# schematic.net
KiCad netlist of a schematic drawn in EAGLE
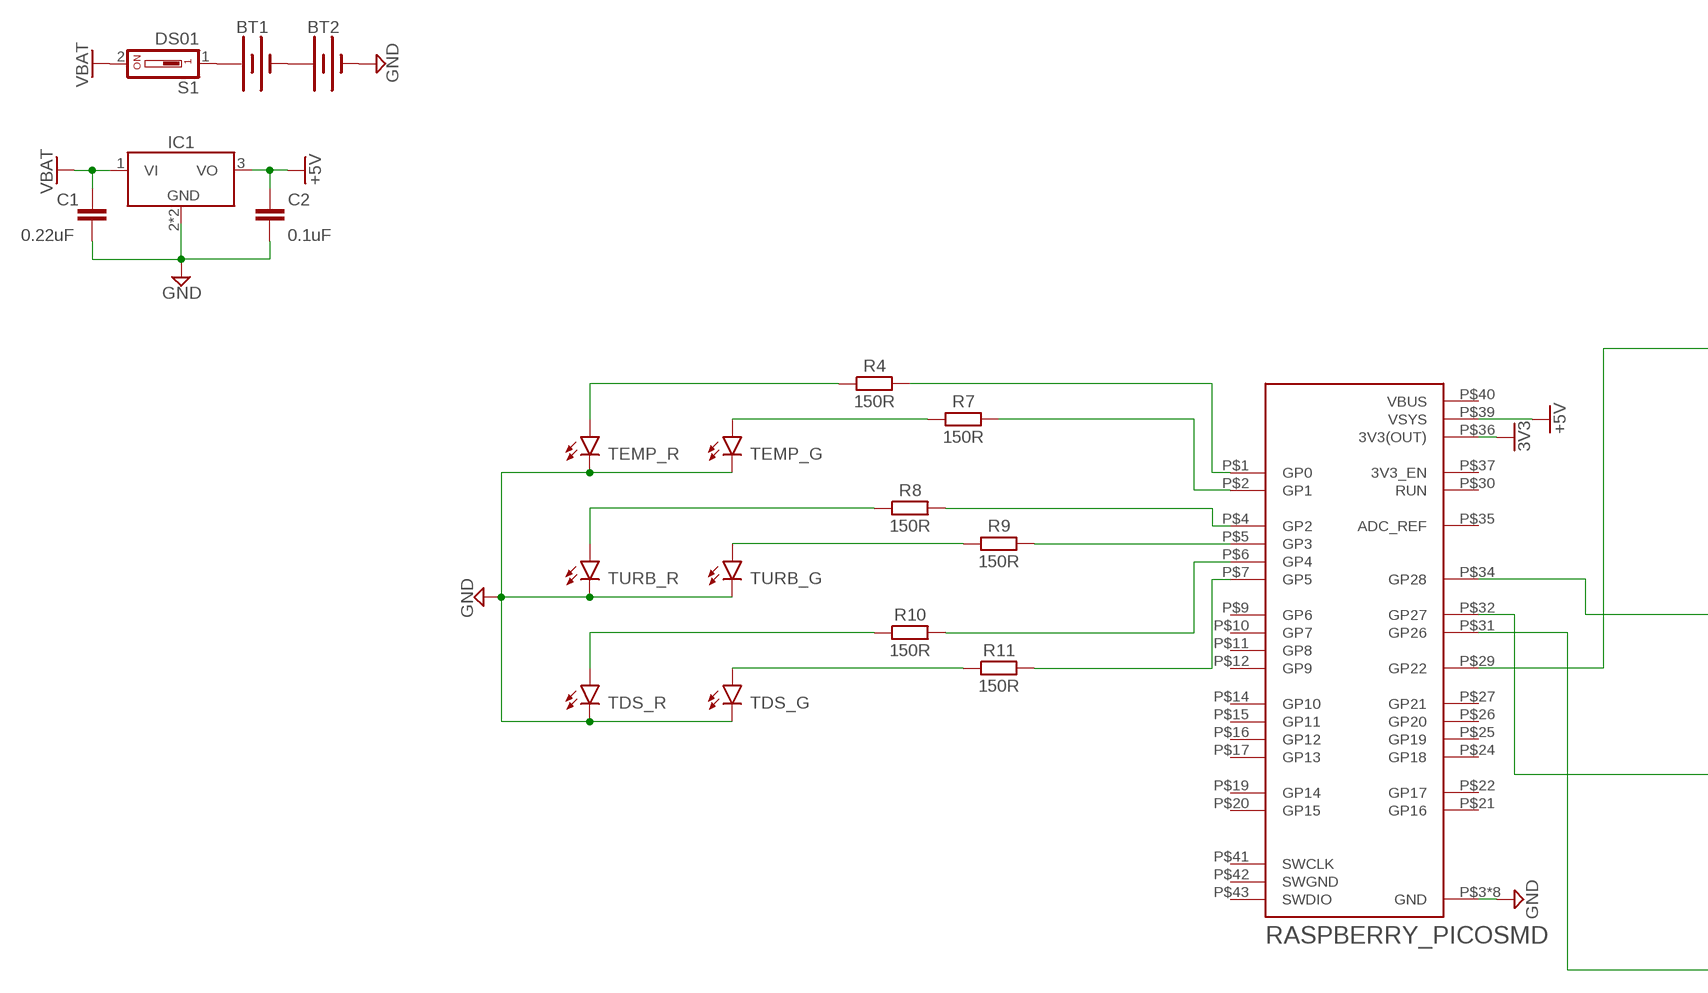
[diagram p0: schematic, sheet 1, part 1 of 2]
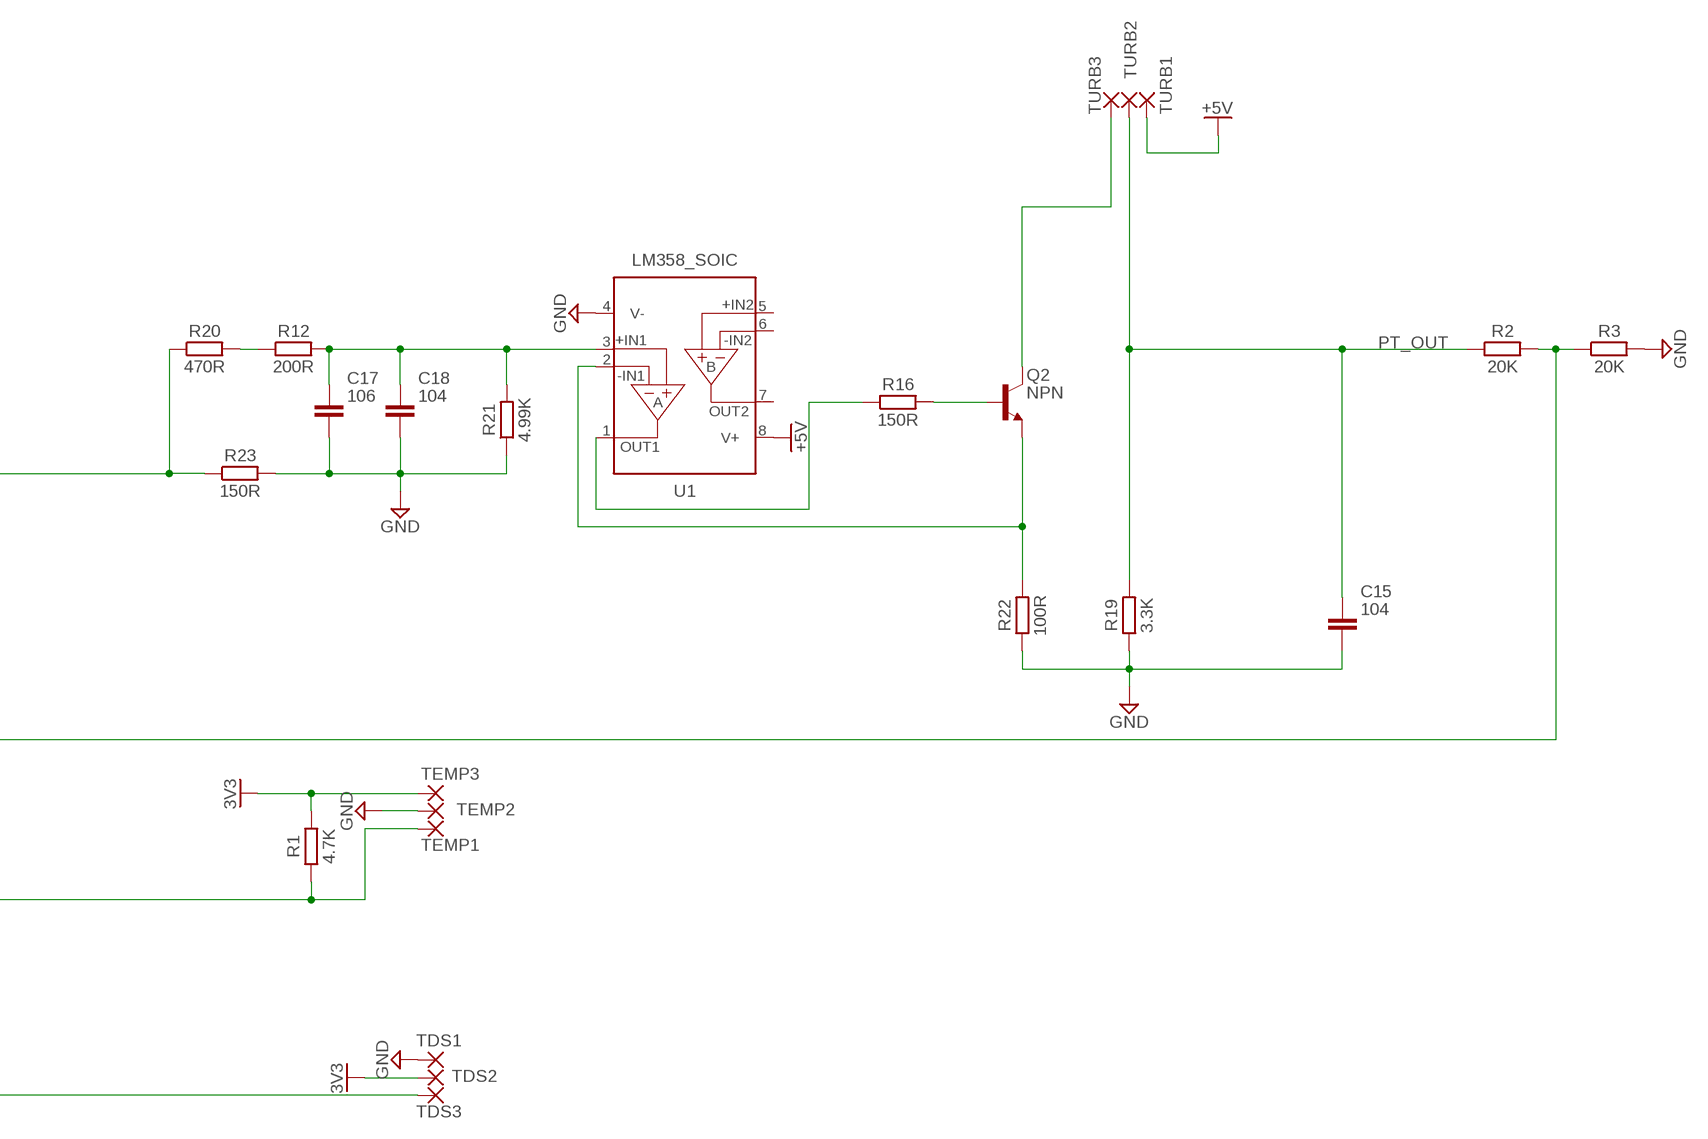
[diagram p1: schematic, sheet 1, part 2 of 2]

(export (version "E")
  (design (tool "Eeschema 10.0.6"))
  (components
    (comp (ref "BT1")
      (value "BATTERY-20MM_SMD_4LEGS")
      (footprint "eagle-import:BATTCON_20MM_4LEGS")
      (libsource (lib "eagle-import") (part "BATTERY-20MM_SMD_4LEGS"))
    )
    (comp (ref "BT2")
      (value "BATTERY-20MM_SMD_4LEGS")
      (footprint "eagle-import:BATTCON_20MM_4LEGS")
      (libsource (lib "eagle-import") (part "BATTERY-20MM_SMD_4LEGS"))
    )
    (comp (ref "C1")
      (value "0.22uF")
      (footprint "eagle-import:CAPC1608X85")
      (libsource (lib "eagle-import") (part "Capacitor_16290819_CCHIP-0603(1608-METRIC)_"))
    )
    (comp (ref "C2")
      (value "0.1uF")
      (footprint "eagle-import:CAPC1608X85")
      (libsource (lib "eagle-import") (part "Capacitor_16290819_CCHIP-0603(1608-METRIC)_"))
    )
    (comp (ref "C15")
      (value "104")
      (footprint "eagle-import:CAPC1005X60")
      (libsource (lib "eagle-import") (part "CCHIP-0402(1005-METRIC)_"))
    )
    (comp (ref "C17")
      (value "106")
      (footprint "eagle-import:CAPC1005X60")
      (libsource (lib "eagle-import") (part "CCHIP-0402(1005-METRIC)_"))
    )
    (comp (ref "C18")
      (value "104")
      (footprint "eagle-import:CAPC1005X60")
      (libsource (lib "eagle-import") (part "CCHIP-0402(1005-METRIC)_"))
    )
    (comp (ref "IC1")
      (value "LM7805_SOT223")
      (footprint "eagle-import:SOT230P700X170-4")
      (fields (field (name "MANUFACTURER") "Generic"))
      (libsource (lib "eagle-import") (part "LM7805_SOT223"))
    )
    (comp (ref "Q2")
      (value "NPN")
      (footprint "eagle-import:SOT95P237X112-3N")
      (libsource (lib "eagle-import") (part "NPNSOT23-BEC_"))
    )
    (comp (ref "R1")
      (value "4.7K")
      (footprint "eagle-import:RESC1005X40")
      (libsource (lib "eagle-import") (part "RCHIP-0402(1005-METRIC)_"))
    )
    (comp (ref "R2")
      (value "20K")
      (footprint "eagle-import:RESC1005X40")
      (libsource (lib "eagle-import") (part "RCHIP-0402(1005-METRIC)_"))
    )
    (comp (ref "R3")
      (value "20K")
      (footprint "eagle-import:RESC1005X40")
      (libsource (lib "eagle-import") (part "RCHIP-0402(1005-METRIC)_"))
    )
    (comp (ref "R4")
      (value "150R")
      (footprint "eagle-import:RESC1005X40")
      (libsource (lib "eagle-import") (part "RCHIP-0402(1005-METRIC)_"))
    )
    (comp (ref "R7")
      (value "150R")
      (footprint "eagle-import:RESC1005X40")
      (libsource (lib "eagle-import") (part "RCHIP-0402(1005-METRIC)_"))
    )
    (comp (ref "R8")
      (value "150R")
      (footprint "eagle-import:RESC1005X40")
      (libsource (lib "eagle-import") (part "RCHIP-0402(1005-METRIC)_"))
    )
    (comp (ref "R9")
      (value "150R")
      (footprint "eagle-import:RESC1005X40")
      (libsource (lib "eagle-import") (part "RCHIP-0402(1005-METRIC)_"))
    )
    (comp (ref "R10")
      (value "150R")
      (footprint "eagle-import:RESC1005X40")
      (libsource (lib "eagle-import") (part "RCHIP-0402(1005-METRIC)_"))
    )
    (comp (ref "R11")
      (value "150R")
      (footprint "eagle-import:RESC1005X40")
      (libsource (lib "eagle-import") (part "RCHIP-0402(1005-METRIC)_"))
    )
    (comp (ref "R12")
      (value "200R")
      (footprint "eagle-import:RESC1005X40")
      (libsource (lib "eagle-import") (part "RCHIP-0402(1005-METRIC)_"))
    )
    (comp (ref "R16")
      (value "150R")
      (footprint "eagle-import:RESC1005X40")
      (libsource (lib "eagle-import") (part "RCHIP-0402(1005-METRIC)_"))
    )
    (comp (ref "R19")
      (value "3.3K")
      (footprint "eagle-import:RESC1005X40")
      (libsource (lib "eagle-import") (part "RCHIP-0402(1005-METRIC)_"))
    )
    (comp (ref "R20")
      (value "470R")
      (footprint "eagle-import:RESC1005X40")
      (libsource (lib "eagle-import") (part "RCHIP-0402(1005-METRIC)_"))
    )
    (comp (ref "R21")
      (value "4.99K")
      (footprint "eagle-import:RESC1608X60")
      (libsource (lib "eagle-import") (part "RCHIP-0603(1608-METRIC)_"))
    )
    (comp (ref "R22")
      (value "100R")
      (footprint "eagle-import:RESC1005X40")
      (libsource (lib "eagle-import") (part "RCHIP-0402(1005-METRIC)_"))
    )
    (comp (ref "R23")
      (value "150R")
      (footprint "eagle-import:RESC1005X40")
      (libsource (lib "eagle-import") (part "RCHIP-0402(1005-METRIC)_"))
    )
    (comp (ref "S1")
      (value "DS01")
      (footprint "eagle-import:DS-01")
      (libsource (lib "eagle-import") (part "DS01"))
    )
    (comp (ref "TDS1")
      (value "SMD5")
      (footprint "eagle-import:SMD2,54-5,08")
      (libsource (lib "eagle-import") (part "SMD5"))
    )
    (comp (ref "TDS2")
      (value "SMD5")
      (footprint "eagle-import:SMD2,54-5,08")
      (libsource (lib "eagle-import") (part "SMD5"))
    )
    (comp (ref "TDS3")
      (value "SMD5")
      (footprint "eagle-import:SMD2,54-5,08")
      (libsource (lib "eagle-import") (part "SMD5"))
    )
    (comp (ref "TDS_G")
      (value "CHIP-ROUND-G_0805")
      (footprint "eagle-import:LEDC2012X105N_RND-G")
      (libsource (lib "eagle-import") (part "CHIP-ROUND-G_0805"))
    )
    (comp (ref "TDS_R")
      (value "CHIP-ROUND-R_0805")
      (footprint "eagle-import:LEDC2012X105N_RND-R")
      (libsource (lib "eagle-import") (part "CHIP-ROUND-R_0805"))
    )
    (comp (ref "TEMP1")
      (value "SMD5")
      (footprint "eagle-import:SMD2,54-5,08")
      (libsource (lib "eagle-import") (part "SMD5"))
    )
    (comp (ref "TEMP2")
      (value "SMD5")
      (footprint "eagle-import:SMD2,54-5,08")
      (libsource (lib "eagle-import") (part "SMD5"))
    )
    (comp (ref "TEMP3")
      (value "SMD5")
      (footprint "eagle-import:SMD2,54-5,08")
      (libsource (lib "eagle-import") (part "SMD5"))
    )
    (comp (ref "TEMP_G")
      (value "CHIP-ROUND-G_0805")
      (footprint "eagle-import:LEDC2012X105N_RND-G")
      (libsource (lib "eagle-import") (part "CHIP-ROUND-G_0805"))
    )
    (comp (ref "TEMP_R")
      (value "CHIP-ROUND-R_0805")
      (footprint "eagle-import:LEDC2012X105N_RND-R")
      (libsource (lib "eagle-import") (part "CHIP-ROUND-R_0805"))
    )
    (comp (ref "TURB1")
      (value "SMD5")
      (footprint "eagle-import:SMD2,54-5,08")
      (libsource (lib "eagle-import") (part "SMD5"))
    )
    (comp (ref "TURB2")
      (value "SMD5")
      (footprint "eagle-import:SMD2,54-5,08")
      (libsource (lib "eagle-import") (part "SMD5"))
    )
    (comp (ref "TURB3")
      (value "SMD5")
      (footprint "eagle-import:SMD2,54-5,08")
      (libsource (lib "eagle-import") (part "SMD5"))
    )
    (comp (ref "TURB_G")
      (value "CHIP-ROUND-G_0805")
      (footprint "eagle-import:LEDC2012X105N_RND-G")
      (libsource (lib "eagle-import") (part "CHIP-ROUND-G_0805"))
    )
    (comp (ref "TURB_R")
      (value "CHIP-ROUND-R_0805")
      (footprint "eagle-import:LEDC2012X105N_RND-R")
      (libsource (lib "eagle-import") (part "CHIP-ROUND-R_0805"))
    )
    (comp (ref "U1")
      (value "LM358_SOIC")
      (footprint "eagle-import:SOIC127P600X175-8N")
      (fields (field (name "MANUFACTURER") "Generic"))
      (libsource (lib "eagle-import") (part "LM358_SOIC"))
    )
    (comp (ref "U2")
      (value "RASPBERRY_PICOSMD")
      (footprint "eagle-import:PICO-PKG-SMD")
      (libsource (lib "eagle-import") (part "RASPBERRY_PICOSMD"))
    )
  )
  (nets
    (net (code "1") (name "+5V") (class "Default")
      (node (ref "C2") (pin "1") (pinfunction "1_1") (pintype "passive"))
      (node (ref "IC1") (pin "3") (pinfunction "VO_3") (pintype "output"))
      (node (ref "TURB1") (pin "1") (pinfunction "P_1") (pintype "passive"))
      (node (ref "U1") (pin "8") (pinfunction "V+_8") (pintype "bidirectional"))
      (node (ref "U2") (pin "P$39") (pinfunction "VSYS_P$39") (pintype "power_in"))
    )
    (net (code "2") (name "/PT_OUT") (class "Default")
      (node (ref "C15") (pin "1") (pinfunction "1_1") (pintype "passive"))
      (node (ref "R19") (pin "2") (pinfunction "2_2") (pintype "passive"))
      (node (ref "R2") (pin "1") (pinfunction "1_1") (pintype "passive"))
      (node (ref "TURB2") (pin "1") (pinfunction "P_1") (pintype "passive"))
    )
    (net (code "3") (name "/SWGND") (class "Default")
      (node (ref "U2") (pin "P$42") (pinfunction "SWGND_P$42") (pintype "power_in"))
    )
    (net (code "4") (name "/VBUS") (class "Default")
      (node (ref "U2") (pin "P$40") (pinfunction "VBUS_P$40") (pintype "power_in"))
    )
    (net (code "5") (name "3V3") (class "Default")
      (node (ref "R1") (pin "2") (pinfunction "2_2") (pintype "passive"))
      (node (ref "TDS2") (pin "1") (pinfunction "P_1") (pintype "passive"))
      (node (ref "TEMP3") (pin "1") (pinfunction "P_1") (pintype "passive"))
      (node (ref "U2") (pin "P$36") (pinfunction "3V3(OUT)_P$36") (pintype "power_in"))
    )
    (net (code "6") (name "GND") (class "Default")
      (node (ref "BT2") (pin "NEGATIVE") (pinfunction "-_NEGATIVE") (pintype "power_in"))
      (node (ref "C1") (pin "2") (pinfunction "2_2") (pintype "passive"))
      (node (ref "C15") (pin "2") (pinfunction "2_2") (pintype "passive"))
      (node (ref "C17") (pin "2") (pinfunction "2_2") (pintype "passive"))
      (node (ref "C18") (pin "2") (pinfunction "2_2") (pintype "passive"))
      (node (ref "C2") (pin "2") (pinfunction "2_2") (pintype "passive"))
      (node (ref "IC1") (pin "2") (pinfunction "GND_2") (pintype "passive"))
      (node (ref "IC1") (pin "4") (pinfunction "GND_4") (pintype "passive"))
      (node (ref "R19") (pin "1") (pinfunction "1_1") (pintype "passive"))
      (node (ref "R21") (pin "1") (pinfunction "1_1") (pintype "passive"))
      (node (ref "R22") (pin "1") (pinfunction "1_1") (pintype "passive"))
      (node (ref "R23") (pin "2") (pinfunction "2_2") (pintype "passive"))
      (node (ref "R3") (pin "2") (pinfunction "2_2") (pintype "passive"))
      (node (ref "TDS1") (pin "1") (pinfunction "P_1") (pintype "passive"))
      (node (ref "TDS_G") (pin "C") (pinfunction "C_C") (pintype "passive"))
      (node (ref "TDS_R") (pin "C") (pinfunction "C_C") (pintype "passive"))
      (node (ref "TEMP2") (pin "1") (pinfunction "P_1") (pintype "passive"))
      (node (ref "TEMP_G") (pin "C") (pinfunction "C_C") (pintype "passive"))
      (node (ref "TEMP_R") (pin "C") (pinfunction "C_C") (pintype "passive"))
      (node (ref "TURB_G") (pin "C") (pinfunction "C_C") (pintype "passive"))
      (node (ref "TURB_R") (pin "C") (pinfunction "C_C") (pintype "passive"))
      (node (ref "U1") (pin "4") (pinfunction "V-_4") (pintype "bidirectional"))
      (node (ref "U2") (pin "P$13") (pinfunction "GND_P$13") (pintype "power_in"))
      (node (ref "U2") (pin "P$18") (pinfunction "GND_P$18") (pintype "power_in"))
      (node (ref "U2") (pin "P$23") (pinfunction "GND_P$23") (pintype "power_in"))
      (node (ref "U2") (pin "P$28") (pinfunction "GND_P$28") (pintype "power_in"))
      (node (ref "U2") (pin "P$3") (pinfunction "GND_P$3") (pintype "power_in"))
      (node (ref "U2") (pin "P$33") (pinfunction "GND_P$33") (pintype "power_in"))
      (node (ref "U2") (pin "P$38") (pinfunction "GND_P$38") (pintype "power_in"))
      (node (ref "U2") (pin "P$8") (pinfunction "GND_P$8") (pintype "power_in"))
    )
    (net (code "7") (name "Net-(BT1-+-PadPOSITIVE@1)") (class "Default")
      (node (ref "BT1") (pin "POSITIVE@1") (pinfunction "+_POSITIVE@1") (pintype "power_in"))
      (node (ref "BT1") (pin "POSITIVE@2") (pinfunction "+_POSITIVE@2") (pintype "power_in"))
      (node (ref "BT1") (pin "POSITIVE@3") (pinfunction "+_POSITIVE@3") (pintype "power_in"))
      (node (ref "BT1") (pin "POSITIVE@4") (pinfunction "+_POSITIVE@4") (pintype "power_in"))
      (node (ref "S1") (pin "1") (pinfunction "1_1") (pintype "passive"))
    )
    (net (code "8") (name "Net-(BT1--)") (class "Default")
      (node (ref "BT1") (pin "NEGATIVE") (pinfunction "-_NEGATIVE") (pintype "power_in"))
      (node (ref "BT2") (pin "POSITIVE@1") (pinfunction "+_POSITIVE@1") (pintype "power_in"))
      (node (ref "BT2") (pin "POSITIVE@2") (pinfunction "+_POSITIVE@2") (pintype "power_in"))
      (node (ref "BT2") (pin "POSITIVE@3") (pinfunction "+_POSITIVE@3") (pintype "power_in"))
      (node (ref "BT2") (pin "POSITIVE@4") (pinfunction "+_POSITIVE@4") (pintype "power_in"))
    )
    (net (code "9") (name "Net-(Q2-B)") (class "Default")
      (node (ref "Q2") (pin "1") (pinfunction "B_1") (pintype "passive"))
      (node (ref "R16") (pin "2") (pinfunction "2_2") (pintype "passive"))
    )
    (net (code "10") (name "Net-(Q2-C)") (class "Default")
      (node (ref "Q2") (pin "3") (pinfunction "C_3") (pintype "passive"))
      (node (ref "TURB3") (pin "1") (pinfunction "P_1") (pintype "passive"))
    )
    (net (code "11") (name "Net-(Q2-E)") (class "Default")
      (node (ref "Q2") (pin "2") (pinfunction "E_2") (pintype "passive"))
      (node (ref "R22") (pin "2") (pinfunction "2_2") (pintype "passive"))
      (node (ref "U1") (pin "2") (pinfunction "-IN1_2") (pintype "input"))
    )
    (net (code "12") (name "Net-(R4-Pad1)") (class "Default")
      (node (ref "R4") (pin "1") (pinfunction "1_1") (pintype "passive"))
      (node (ref "TEMP_R") (pin "A") (pinfunction "A_A") (pintype "passive"))
    )
    (net (code "13") (name "Net-(R7-Pad1)") (class "Default")
      (node (ref "R7") (pin "1") (pinfunction "1_1") (pintype "passive"))
      (node (ref "TEMP_G") (pin "A") (pinfunction "A_A") (pintype "passive"))
    )
    (net (code "14") (name "Net-(R8-Pad1)") (class "Default")
      (node (ref "R8") (pin "1") (pinfunction "1_1") (pintype "passive"))
      (node (ref "TURB_R") (pin "A") (pinfunction "A_A") (pintype "passive"))
    )
    (net (code "15") (name "Net-(R9-Pad1)") (class "Default")
      (node (ref "R9") (pin "1") (pinfunction "1_1") (pintype "passive"))
      (node (ref "TURB_G") (pin "A") (pinfunction "A_A") (pintype "passive"))
    )
    (net (code "16") (name "Net-(R10-Pad1)") (class "Default")
      (node (ref "R10") (pin "1") (pinfunction "1_1") (pintype "passive"))
      (node (ref "TDS_R") (pin "A") (pinfunction "A_A") (pintype "passive"))
    )
    (net (code "17") (name "Net-(R11-Pad1)") (class "Default")
      (node (ref "R11") (pin "1") (pinfunction "1_1") (pintype "passive"))
      (node (ref "TDS_G") (pin "A") (pinfunction "A_A") (pintype "passive"))
    )
    (net (code "18") (name "Net-(R12-Pad1)") (class "Default")
      (node (ref "R12") (pin "1") (pinfunction "1_1") (pintype "passive"))
      (node (ref "R20") (pin "2") (pinfunction "2_2") (pintype "passive"))
    )
    (net (code "19") (name "Net-(TDS3-P)") (class "Default")
      (node (ref "TDS3") (pin "1") (pinfunction "P_1") (pintype "passive"))
      (node (ref "U2") (pin "P$31") (pinfunction "GP26_P$31") (pintype "bidirectional"))
    )
    (net (code "20") (name "Net-(TEMP1-P)") (class "Default")
      (node (ref "R1") (pin "1") (pinfunction "1_1") (pintype "passive"))
      (node (ref "TEMP1") (pin "1") (pinfunction "P_1") (pintype "passive"))
      (node (ref "U2") (pin "P$32") (pinfunction "GP27_P$32") (pintype "bidirectional"))
    )
    (net (code "21") (name "Net-(U1-+IN1)") (class "Default")
      (node (ref "C17") (pin "1") (pinfunction "1_1") (pintype "passive"))
      (node (ref "C18") (pin "1") (pinfunction "1_1") (pintype "passive"))
      (node (ref "R12") (pin "2") (pinfunction "2_2") (pintype "passive"))
      (node (ref "R21") (pin "2") (pinfunction "2_2") (pintype "passive"))
      (node (ref "U1") (pin "3") (pinfunction "+IN1_3") (pintype "input"))
    )
    (net (code "22") (name "Net-(U1-OUT1)") (class "Default")
      (node (ref "R16") (pin "1") (pinfunction "1_1") (pintype "passive"))
      (node (ref "U1") (pin "1") (pinfunction "OUT1_1") (pintype "passive"))
    )
    (net (code "23") (name "Net-(U2-GP0)") (class "Default")
      (node (ref "R4") (pin "2") (pinfunction "2_2") (pintype "passive"))
      (node (ref "U2") (pin "P$1") (pinfunction "GP0_P$1") (pintype "bidirectional"))
    )
    (net (code "24") (name "Net-(U2-GP1)") (class "Default")
      (node (ref "R7") (pin "2") (pinfunction "2_2") (pintype "passive"))
      (node (ref "U2") (pin "P$2") (pinfunction "GP1_P$2") (pintype "bidirectional"))
    )
    (net (code "25") (name "Net-(U2-GP2)") (class "Default")
      (node (ref "R8") (pin "2") (pinfunction "2_2") (pintype "passive"))
      (node (ref "U2") (pin "P$4") (pinfunction "GP2_P$4") (pintype "bidirectional"))
    )
    (net (code "26") (name "Net-(U2-GP3)") (class "Default")
      (node (ref "R9") (pin "2") (pinfunction "2_2") (pintype "passive"))
      (node (ref "U2") (pin "P$5") (pinfunction "GP3_P$5") (pintype "bidirectional"))
    )
    (net (code "27") (name "Net-(U2-GP4)") (class "Default")
      (node (ref "R10") (pin "2") (pinfunction "2_2") (pintype "passive"))
      (node (ref "U2") (pin "P$6") (pinfunction "GP4_P$6") (pintype "bidirectional"))
    )
    (net (code "28") (name "Net-(U2-GP5)") (class "Default")
      (node (ref "R11") (pin "2") (pinfunction "2_2") (pintype "passive"))
      (node (ref "U2") (pin "P$7") (pinfunction "GP5_P$7") (pintype "bidirectional"))
    )
    (net (code "29") (name "Net-(U2-GP22)") (class "Default")
      (node (ref "R20") (pin "1") (pinfunction "1_1") (pintype "passive"))
      (node (ref "R23") (pin "1") (pinfunction "1_1") (pintype "passive"))
      (node (ref "U2") (pin "P$29") (pinfunction "GP22_P$29") (pintype "bidirectional"))
    )
    (net (code "30") (name "Net-(U2-GP28)") (class "Default")
      (node (ref "R2") (pin "2") (pinfunction "2_2") (pintype "passive"))
      (node (ref "R3") (pin "1") (pinfunction "1_1") (pintype "passive"))
      (node (ref "U2") (pin "P$34") (pinfunction "GP28_P$34") (pintype "bidirectional"))
    )
    (net (code "31") (name "VBAT") (class "Default")
      (node (ref "C1") (pin "1") (pinfunction "1_1") (pintype "passive"))
      (node (ref "IC1") (pin "1") (pinfunction "VI_1") (pintype "input"))
      (node (ref "S1") (pin "2") (pinfunction "2_2") (pintype "passive"))
    )
    (net (code "32") (name "unconnected-(U1-+IN2-Pad5)") (class "Default")
      (node (ref "U1") (pin "5") (pinfunction "+IN2_5") (pintype "passive"))
    )
    (net (code "33") (name "unconnected-(U1--IN2-Pad6)") (class "Default")
      (node (ref "U1") (pin "6") (pinfunction "-IN2_6") (pintype "passive"))
    )
    (net (code "34") (name "unconnected-(U1-OUT2-Pad7)") (class "Default")
      (node (ref "U1") (pin "7") (pinfunction "OUT2_7") (pintype "passive"))
    )
    (net (code "35") (name "unconnected-(U2-3V3_EN-PadP$37)") (class "Default")
      (node (ref "U2") (pin "P$37") (pinfunction "3V3_EN_P$37") (pintype "input"))
    )
    (net (code "36") (name "unconnected-(U2-ADC_REF-PadP$35)") (class "Default")
      (node (ref "U2") (pin "P$35") (pinfunction "ADC_REF_P$35") (pintype "input"))
    )
    (net (code "37") (name "unconnected-(U2-GP6-PadP$9)") (class "Default")
      (node (ref "U2") (pin "P$9") (pinfunction "GP6_P$9") (pintype "bidirectional"))
    )
    (net (code "38") (name "unconnected-(U2-GP7-PadP$10)") (class "Default")
      (node (ref "U2") (pin "P$10") (pinfunction "GP7_P$10") (pintype "bidirectional"))
    )
    (net (code "39") (name "unconnected-(U2-GP8-PadP$11)") (class "Default")
      (node (ref "U2") (pin "P$11") (pinfunction "GP8_P$11") (pintype "bidirectional"))
    )
    (net (code "40") (name "unconnected-(U2-GP9-PadP$12)") (class "Default")
      (node (ref "U2") (pin "P$12") (pinfunction "GP9_P$12") (pintype "bidirectional"))
    )
    (net (code "41") (name "unconnected-(U2-GP10-PadP$14)") (class "Default")
      (node (ref "U2") (pin "P$14") (pinfunction "GP10_P$14") (pintype "bidirectional"))
    )
    (net (code "42") (name "unconnected-(U2-GP11-PadP$15)") (class "Default")
      (node (ref "U2") (pin "P$15") (pinfunction "GP11_P$15") (pintype "bidirectional"))
    )
    (net (code "43") (name "unconnected-(U2-GP12-PadP$16)") (class "Default")
      (node (ref "U2") (pin "P$16") (pinfunction "GP12_P$16") (pintype "bidirectional"))
    )
    (net (code "44") (name "unconnected-(U2-GP13-PadP$17)") (class "Default")
      (node (ref "U2") (pin "P$17") (pinfunction "GP13_P$17") (pintype "bidirectional"))
    )
    (net (code "45") (name "unconnected-(U2-GP14-PadP$19)") (class "Default")
      (node (ref "U2") (pin "P$19") (pinfunction "GP14_P$19") (pintype "bidirectional"))
    )
    (net (code "46") (name "unconnected-(U2-GP15-PadP$20)") (class "Default")
      (node (ref "U2") (pin "P$20") (pinfunction "GP15_P$20") (pintype "bidirectional"))
    )
    (net (code "47") (name "unconnected-(U2-GP16-PadP$21)") (class "Default")
      (node (ref "U2") (pin "P$21") (pinfunction "GP16_P$21") (pintype "bidirectional"))
    )
    (net (code "48") (name "unconnected-(U2-GP17-PadP$22)") (class "Default")
      (node (ref "U2") (pin "P$22") (pinfunction "GP17_P$22") (pintype "bidirectional"))
    )
    (net (code "49") (name "unconnected-(U2-GP18-PadP$24)") (class "Default")
      (node (ref "U2") (pin "P$24") (pinfunction "GP18_P$24") (pintype "bidirectional"))
    )
    (net (code "50") (name "unconnected-(U2-GP19-PadP$25)") (class "Default")
      (node (ref "U2") (pin "P$25") (pinfunction "GP19_P$25") (pintype "bidirectional"))
    )
    (net (code "51") (name "unconnected-(U2-GP20-PadP$26)") (class "Default")
      (node (ref "U2") (pin "P$26") (pinfunction "GP20_P$26") (pintype "bidirectional"))
    )
    (net (code "52") (name "unconnected-(U2-GP21-PadP$27)") (class "Default")
      (node (ref "U2") (pin "P$27") (pinfunction "GP21_P$27") (pintype "bidirectional"))
    )
    (net (code "53") (name "unconnected-(U2-RUN-PadP$30)") (class "Default")
      (node (ref "U2") (pin "P$30") (pinfunction "RUN_P$30") (pintype "input"))
    )
    (net (code "54") (name "unconnected-(U2-SWCLK-PadP$41)") (class "Default")
      (node (ref "U2") (pin "P$41") (pinfunction "SWCLK_P$41") (pintype "input"))
    )
    (net (code "55") (name "unconnected-(U2-SWDIO-PadP$43)") (class "Default")
      (node (ref "U2") (pin "P$43") (pinfunction "SWDIO_P$43") (pintype "bidirectional"))
    )
  )
)
